# SpeakEasy_Power_Connectors.net
KiCad netlist of a schematic drawn in Altium Designer
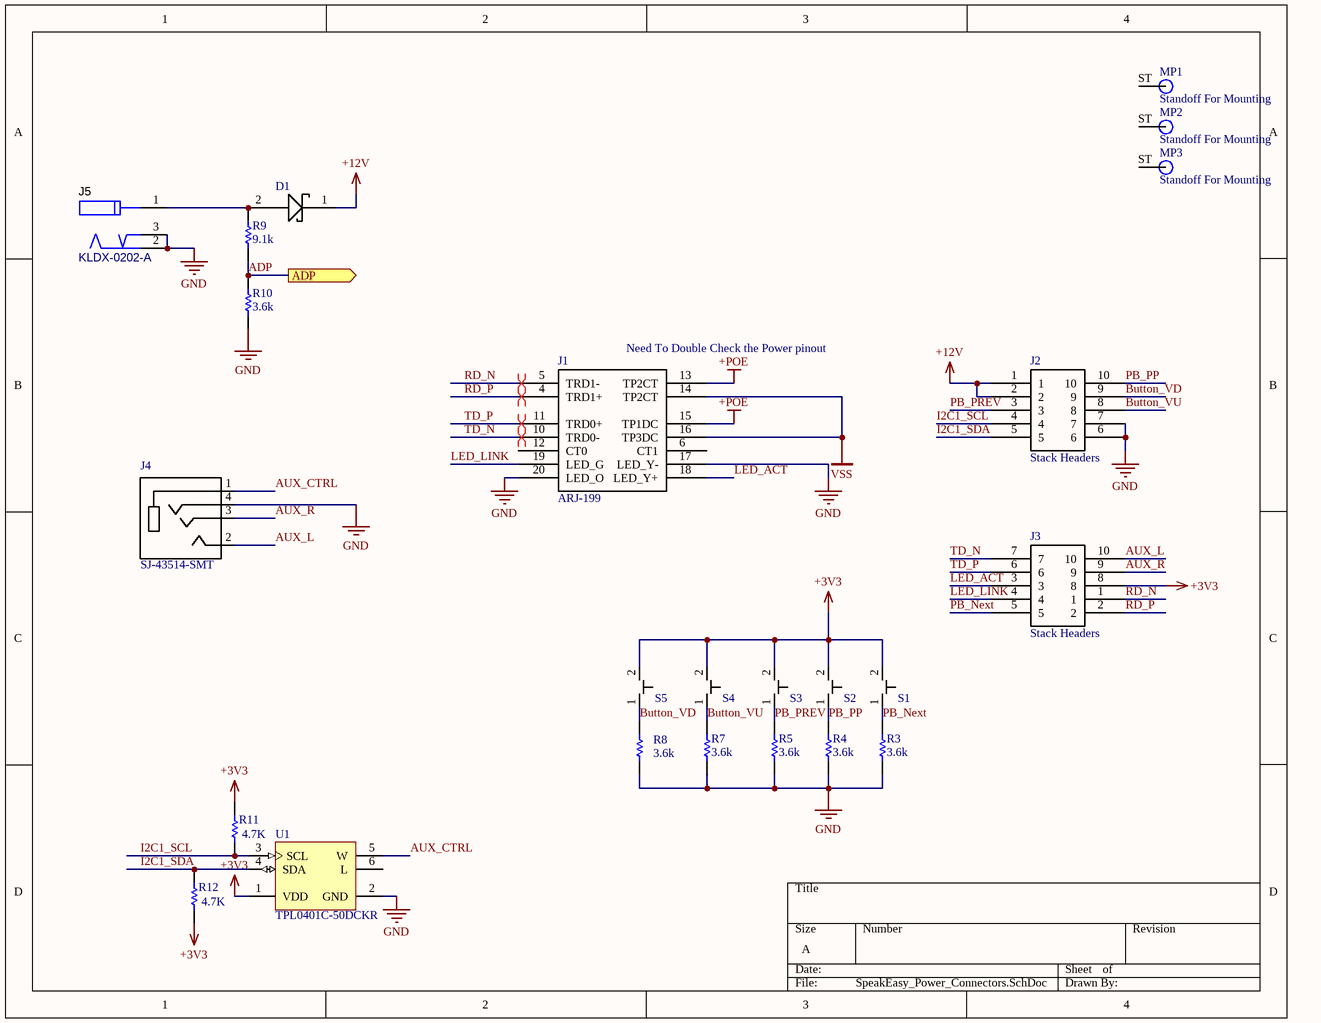
[diagram p0: SpeakEasy_Power_Connectors.SchDoc]

(export (version "E")
  (design (tool "Eeschema 10.0.6"))
  (components
    (comp (ref "D1")
      (value "Shottkey Diode")
      (footprint "DO-220AA")
      (libsource (lib "SpeakEasy") (part "V3P6"))
    )
    (comp (ref "J1")
      (value "ARJ-199")
      (footprint "ARJ-199")
      (description "MagJack POE+ Jack")
      (libsource (lib "SpeakEasy") (part "ARJ-199"))
    )
    (comp (ref "J2")
      (value "Stack Headers")
      (footprint "TSW-105")
      (libsource (lib "SpeakEasy") (part "Stack Headers"))
    )
    (comp (ref "J3")
      (value "Stack Headers")
      (footprint "TSW-105")
      (libsource (lib "") (part "Stack Headers_1"))
    )
    (comp (ref "J4")
      (value "SJ-43514-SMT")
      (footprint "CUI_SJ-43514-SMT")
      (libsource (lib "SJ-43514-SMT") (part "SJ-43514-SMT"))
    )
    (comp (ref "J5")
      (value "KLDX-0202-A")
      (footprint "KYCN-KLDX-0202-A_V")
      (description "DC Power Connectors 2mm PCB JACK POWER JACK")
      (libsource (lib "Altium Content Vault") (part "CONN_DC JACK"))
    )
    (comp (ref "MP1")
      (value "Standoff For Mounting")
      (footprint "STO")
      (libsource (lib "SpeakEasy") (part "Standoff"))
    )
    (comp (ref "MP2")
      (value "Standoff For Mounting")
      (footprint "STO")
      (libsource (lib "SpeakEasy") (part "Standoff"))
    )
    (comp (ref "MP3")
      (value "Standoff For Mounting")
      (footprint "STO")
      (libsource (lib "SpeakEasy") (part "Standoff"))
    )
    (comp (ref "R3")
      (value "3.6k")
      (footprint "RESC0805(2012)_L")
      (description "0805 (2012 Metric) Chip Resistor")
      (libsource (lib "Altium Content Vault") (part "RES_3"))
    )
    (comp (ref "R4")
      (value "3.6k")
      (footprint "RESC0805(2012)_L")
      (description "0805 (2012 Metric) Chip Resistor")
      (libsource (lib "Altium Content Vault") (part "RES_3"))
    )
    (comp (ref "R5")
      (value "3.6k")
      (footprint "RESC0805(2012)_L")
      (description "0805 (2012 Metric) Chip Resistor")
      (libsource (lib "Altium Content Vault") (part "RES_3"))
    )
    (comp (ref "R7")
      (value "3.6k")
      (footprint "RESC0805(2012)_L")
      (description "0805 (2012 Metric) Chip Resistor")
      (libsource (lib "Altium Content Vault") (part "RES_3"))
    )
    (comp (ref "R8")
      (value "3.6k")
      (footprint "RESC0805(2012)_L")
      (description "0805 (2012 Metric) Chip Resistor")
      (libsource (lib "Altium Content Vault") (part "RES_3"))
    )
    (comp (ref "R9")
      (value "9.1k")
      (footprint "RESC0805(2012)_L")
      (description "0805 (2012 Metric) Chip Resistor")
      (libsource (lib "Altium Content Vault") (part "RES_3"))
    )
    (comp (ref "R10")
      (value "3.6k")
      (footprint "RESC0805(2012)_L")
      (description "0805 (2012 Metric) Chip Resistor")
      (libsource (lib "Altium Content Vault") (part "RES_3"))
    )
    (comp (ref "R11")
      (value "4.7K")
      (footprint "RESC0603(1608)_N")
      (description "100K 0.1W 5% 0603 (1608 Metric)  SMD")
      (fields (field (name "TOLERANCE") "5 %") (field (name "POWER") "0.1 W"))
      (libsource (lib "Altium Content Vault") (part "RES"))
    )
    (comp (ref "R12")
      (value "4.7K")
      (footprint "RESC0603(1608)_N")
      (fields (field (name "TOLERANCE") "5 %") (field (name "POWER") "0.1 W"))
      (libsource (lib "Altium Content Vault") (part "RES"))
    )
    (comp (ref "S1")
      (value "SPST Switch")
      (footprint "TL1105")
      (libsource (lib "SpeakEasy") (part "SPST Switch"))
    )
    (comp (ref "S2")
      (value "SPST Switch")
      (footprint "TL1105")
      (libsource (lib "SpeakEasy") (part "SPST Switch"))
    )
    (comp (ref "S3")
      (value "SPST Switch")
      (footprint "TL1105")
      (libsource (lib "SpeakEasy") (part "SPST Switch"))
    )
    (comp (ref "S4")
      (value "SPST Switch")
      (footprint "TL1105")
      (libsource (lib "SpeakEasy") (part "SPST Switch"))
    )
    (comp (ref "S5")
      (value "SPST Switch")
      (footprint "TL1105")
      (libsource (lib "SpeakEasy") (part "SPST Switch"))
    )
    (comp (ref "U1")
      (value "TPL0401C-50DCKR")
      (footprint "TI-DCK6_V")
      (description "128 Tap Digital Potentiometer with I2C Interface, -40 to 125 degC, 6-pin SOT23 (DCK6)")
      (fields (field (name "MANUFACTURER") "Texas Instruments"))
      (libsource (lib "Altium Content Vault") (part "TI-TPL0401C-50DCK6"))
    )
  )
  (nets
    (net (code "1") (name "+3V3") (class "Default")
      (node (ref "J3") (pin "8") (pinfunction "8_8") (pintype "passive"))
      (node (ref "R11") (pin "2") (pinfunction "2_2") (pintype "passive"))
      (node (ref "R12") (pin "1") (pinfunction "1_1") (pintype "passive"))
      (node (ref "S1") (pin "2") (pinfunction "2_2") (pintype "passive"))
      (node (ref "S2") (pin "2") (pinfunction "2_2") (pintype "passive"))
      (node (ref "S3") (pin "2") (pinfunction "2_2") (pintype "passive"))
      (node (ref "S4") (pin "2") (pinfunction "2_2") (pintype "passive"))
      (node (ref "S5") (pin "2") (pinfunction "2_2") (pintype "passive"))
      (node (ref "U1") (pin "1") (pinfunction "VDD_1") (pintype "power_in"))
    )
    (net (code "2") (name "+12V") (class "Default")
      (node (ref "D1") (pin "1") (pinfunction "-_1") (pintype "passive"))
      (node (ref "J2") (pin "1") (pinfunction "1_1") (pintype "passive"))
      (node (ref "J2") (pin "2") (pinfunction "2_2") (pintype "passive"))
    )
    (net (code "3") (name "+POE") (class "Default")
      (node (ref "J1") (pin "13") (pinfunction "TP2CT_13") (pintype "passive"))
      (node (ref "J1") (pin "15") (pinfunction "TP1DC_15") (pintype "passive"))
    )
    (net (code "4") (name "/ADP") (class "Default")
      (node (ref "R10") (pin "2") (pinfunction "2_2") (pintype "passive"))
      (node (ref "R9") (pin "1") (pinfunction "1_1") (pintype "passive"))
    )
    (net (code "5") (name "/AUX_CTRL") (class "Default")
      (node (ref "J4") (pin "1") (pinfunction "SLEEVE_1") (pintype "passive"))
      (node (ref "U1") (pin "5") (pinfunction "W_5") (pintype "passive"))
    )
    (net (code "6") (name "/AUX_L") (class "Default")
      (node (ref "J3") (pin "10") (pinfunction "10_10") (pintype "passive"))
      (node (ref "J4") (pin "2") (pinfunction "TIP_2") (pintype "passive"))
    )
    (net (code "7") (name "/AUX_R") (class "Default")
      (node (ref "J3") (pin "9") (pinfunction "9_9") (pintype "passive"))
      (node (ref "J4") (pin "3") (pinfunction "RING1_3") (pintype "passive"))
    )
    (net (code "8") (name "/Button_VD") (class "Default")
      (node (ref "J2") (pin "9") (pinfunction "9_9") (pintype "passive"))
      (node (ref "R8") (pin "2") (pinfunction "2_2") (pintype "passive"))
      (node (ref "S5") (pin "1") (pinfunction "1_1") (pintype "passive"))
    )
    (net (code "9") (name "/Button_VU") (class "Default")
      (node (ref "J2") (pin "8") (pinfunction "8_8") (pintype "passive"))
      (node (ref "R7") (pin "2") (pinfunction "2_2") (pintype "passive"))
      (node (ref "S4") (pin "1") (pinfunction "1_1") (pintype "passive"))
    )
    (net (code "10") (name "/I2C1_SCL") (class "Default")
      (node (ref "J2") (pin "4") (pinfunction "4_4") (pintype "passive"))
      (node (ref "R11") (pin "1") (pinfunction "1_1") (pintype "passive"))
      (node (ref "U1") (pin "3") (pinfunction "SCL_3") (pintype "input"))
    )
    (net (code "11") (name "/I2C1_SDA") (class "Default")
      (node (ref "J2") (pin "5") (pinfunction "5_5") (pintype "passive"))
      (node (ref "R12") (pin "2") (pinfunction "2_2") (pintype "passive"))
      (node (ref "U1") (pin "4") (pinfunction "SDA_4") (pintype "bidirectional"))
    )
    (net (code "12") (name "/LED_ACT") (class "Default")
      (node (ref "J1") (pin "18") (pinfunction "LED_Y+_18") (pintype "passive"))
      (node (ref "J3") (pin "3") (pinfunction "3_3") (pintype "passive"))
    )
    (net (code "13") (name "/LED_LINK") (class "Default")
      (node (ref "J1") (pin "19") (pinfunction "LED_G_19") (pintype "passive"))
      (node (ref "J3") (pin "4") (pinfunction "4_4") (pintype "passive"))
    )
    (net (code "14") (name "/PB_Next") (class "Default")
      (node (ref "J3") (pin "5") (pinfunction "5_5") (pintype "passive"))
      (node (ref "R3") (pin "1") (pinfunction "1_1") (pintype "passive"))
      (node (ref "S1") (pin "1") (pinfunction "1_1") (pintype "passive"))
    )
    (net (code "15") (name "/PB_PP") (class "Default")
      (node (ref "J2") (pin "10") (pinfunction "10_10") (pintype "passive"))
      (node (ref "R4") (pin "1") (pinfunction "1_1") (pintype "passive"))
      (node (ref "S2") (pin "1") (pinfunction "1_1") (pintype "passive"))
    )
    (net (code "16") (name "/PB_PREV") (class "Default")
      (node (ref "J2") (pin "3") (pinfunction "3_3") (pintype "passive"))
      (node (ref "R5") (pin "1") (pinfunction "1_1") (pintype "passive"))
      (node (ref "S3") (pin "1") (pinfunction "1_1") (pintype "passive"))
    )
    (net (code "17") (name "/RD_N") (class "Default")
      (node (ref "J1") (pin "5") (pinfunction "TRD1-_5") (pintype "passive"))
      (node (ref "J3") (pin "1") (pinfunction "1_1") (pintype "passive"))
    )
    (net (code "18") (name "/RD_P") (class "Default")
      (node (ref "J1") (pin "4") (pinfunction "TRD1+_4") (pintype "passive"))
      (node (ref "J3") (pin "2") (pinfunction "2_2") (pintype "passive"))
    )
    (net (code "19") (name "/TD_N") (class "Default")
      (node (ref "J1") (pin "10") (pinfunction "TRD0-_10") (pintype "passive"))
      (node (ref "J3") (pin "7") (pinfunction "7_7") (pintype "passive"))
    )
    (net (code "20") (name "/TD_P") (class "Default")
      (node (ref "J1") (pin "11") (pinfunction "TRD0+_11") (pintype "passive"))
      (node (ref "J3") (pin "6") (pinfunction "6_6") (pintype "passive"))
    )
    (net (code "21") (name "GND") (class "Default")
      (node (ref "J1") (pin "17") (pinfunction "LED_Y-_17") (pintype "passive"))
      (node (ref "J1") (pin "20") (pinfunction "LED_O_20") (pintype "passive"))
      (node (ref "J2") (pin "6") (pinfunction "6_6") (pintype "passive"))
      (node (ref "J2") (pin "7") (pinfunction "7_7") (pintype "passive"))
      (node (ref "J4") (pin "4") (pinfunction "RING2_4") (pintype "passive"))
      (node (ref "J5") (pin "2") (pinfunction "2_2") (pintype "passive"))
      (node (ref "J5") (pin "3") (pinfunction "3_3") (pintype "passive"))
      (node (ref "R10") (pin "1") (pinfunction "1_1") (pintype "passive"))
      (node (ref "R3") (pin "2") (pinfunction "2_2") (pintype "passive"))
      (node (ref "R4") (pin "2") (pinfunction "2_2") (pintype "passive"))
      (node (ref "R5") (pin "2") (pinfunction "2_2") (pintype "passive"))
      (node (ref "R7") (pin "1") (pinfunction "1_1") (pintype "passive"))
      (node (ref "R8") (pin "1") (pinfunction "1_1") (pintype "passive"))
      (node (ref "U1") (pin "2") (pinfunction "GND_2") (pintype "power_in"))
    )
    (net (code "22") (name "Net-(D1-+)") (class "Default")
      (node (ref "D1") (pin "2") (pinfunction "+_2") (pintype "passive"))
      (node (ref "J5") (pin "1") (pinfunction "1_1") (pintype "passive"))
      (node (ref "R9") (pin "2") (pinfunction "2_2") (pintype "passive"))
    )
    (net (code "23") (name "VSS") (class "Default")
      (node (ref "J1") (pin "14") (pinfunction "TP2CT_14") (pintype "passive"))
      (node (ref "J1") (pin "16") (pinfunction "TP3DC_16") (pintype "passive"))
    )
    (net (code "24") (name "unconnected-(J1-CT0-Pad12)") (class "Default")
      (node (ref "J1") (pin "12") (pinfunction "CT0_12") (pintype "passive"))
    )
    (net (code "25") (name "unconnected-(J1-CT1-Pad6)") (class "Default")
      (node (ref "J1") (pin "6") (pinfunction "CT1_6") (pintype "passive"))
    )
    (net (code "26") (name "unconnected-(MP1-1-PadST)") (class "Default")
      (node (ref "MP1") (pin "ST") (pinfunction "1_ST") (pintype "passive"))
    )
    (net (code "27") (name "unconnected-(MP2-1-PadST)") (class "Default")
      (node (ref "MP2") (pin "ST") (pinfunction "1_ST") (pintype "passive"))
    )
    (net (code "28") (name "unconnected-(MP3-1-PadST)") (class "Default")
      (node (ref "MP3") (pin "ST") (pinfunction "1_ST") (pintype "passive"))
    )
    (net (code "29") (name "unconnected-(U1-L-Pad6)") (class "Default")
      (node (ref "U1") (pin "6") (pinfunction "L_6") (pintype "passive"))
    )
  )
)
